# TMSS_Final.net
KiCad netlist of a schematic drawn in EAGLE
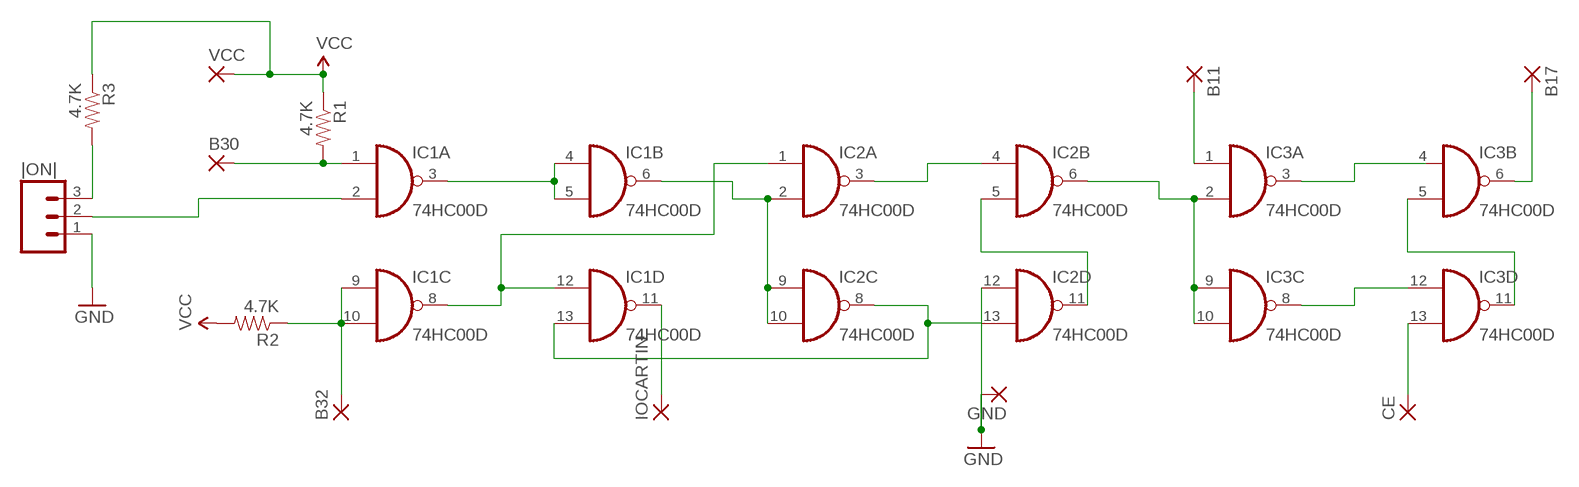
[diagram p0: schematic, sheet 1]

(export (version "E")
  (design (tool "Eeschema 10.0.6"))
  (components
    (comp (ref "B11")
      (value "1,6/0,9")
      (footprint "eagle-import:1,6_0,9")
      (libsource (lib "eagle-import") (part "1,6/0,9"))
    )
    (comp (ref "B17")
      (value "1,6/0,9")
      (footprint "eagle-import:1,6_0,9")
      (libsource (lib "eagle-import") (part "1,6/0,9"))
    )
    (comp (ref "B30")
      (value "1,6/0,9")
      (footprint "eagle-import:1,6_0,9")
      (libsource (lib "eagle-import") (part "1,6/0,9"))
    )
    (comp (ref "B32")
      (value "1,6/0,9")
      (footprint "eagle-import:1,6_0,9")
      (libsource (lib "eagle-import") (part "1,6/0,9"))
    )
    (comp (ref "CE")
      (value "1,6/0,9")
      (footprint "eagle-import:1,6_0,9")
      (libsource (lib "eagle-import") (part "1,6/0,9"))
    )
    (comp (ref "GND")
      (value "1,6/0,9")
      (footprint "eagle-import:1,6_0,9")
      (libsource (lib "eagle-import") (part "1,6/0,9"))
    )
    (comp (ref "IC1")
      (value "74HC00D")
      (footprint "eagle-import:SO14")
      (libsource (lib "eagle-import") (part "7400DHC"))
    )
    (comp (ref "IC2")
      (value "74HC00D")
      (footprint "eagle-import:SO14")
      (libsource (lib "eagle-import") (part "7400DHC"))
    )
    (comp (ref "IC3")
      (value "74HC00D")
      (footprint "eagle-import:SO14")
      (libsource (lib "eagle-import") (part "7400DHC"))
    )
    (comp (ref "IOCARTIN")
      (value "1,6/0,9")
      (footprint "eagle-import:1,6_0,9")
      (libsource (lib "eagle-import") (part "1,6/0,9"))
    )
    (comp (ref "R1")
      (value "4.7K")
      (footprint "eagle-import:0805")
      (libsource (lib "eagle-import") (part "RESISTOR0805-RES"))
    )
    (comp (ref "R2")
      (value "4.7K")
      (footprint "eagle-import:0805")
      (libsource (lib "eagle-import") (part "RESISTOR0805-RES"))
    )
    (comp (ref "R3")
      (value "4.7K")
      (footprint "eagle-import:0805")
      (libsource (lib "eagle-import") (part "RESISTOR0805-RES"))
    )
    (comp (ref "VCC")
      (value "1,6/0,9")
      (footprint "eagle-import:1,6_0,9")
      (libsource (lib "eagle-import") (part "1,6/0,9"))
    )
    (comp (ref "|ON|")
      (value "M03PTH")
      (footprint "eagle-import:1X03")
      (libsource (lib "eagle-import") (part "M03PTH"))
    )
  )
  (nets
    (net (code "1") (name "GND") (class "Default")
      (node (ref "GND") (pin "1") (pinfunction "P_1") (pintype "passive"))
      (node (ref "IC2") (pin "12") (pinfunction "I0_12") (pintype "input"))
      (node (ref "|ON|") (pin "1") (pinfunction "1_1") (pintype "passive"))
    )
    (net (code "2") (name "Net-(B11-P)") (class "Default")
      (node (ref "B11") (pin "1") (pinfunction "P_1") (pintype "passive"))
      (node (ref "IC3") (pin "1") (pinfunction "I0_1") (pintype "input"))
    )
    (net (code "3") (name "Net-(B17-P)") (class "Default")
      (node (ref "B17") (pin "1") (pinfunction "P_1") (pintype "passive"))
      (node (ref "IC3") (pin "6") (pinfunction "O_6") (pintype "output"))
    )
    (net (code "4") (name "Net-(B30-P)") (class "Default")
      (node (ref "B30") (pin "1") (pinfunction "P_1") (pintype "passive"))
      (node (ref "IC1") (pin "1") (pinfunction "I0_1") (pintype "input"))
      (node (ref "R1") (pin "2") (pinfunction "2_2") (pintype "passive"))
    )
    (net (code "5") (name "Net-(B32-P)") (class "Default")
      (node (ref "B32") (pin "1") (pinfunction "P_1") (pintype "passive"))
      (node (ref "IC1") (pin "10") (pinfunction "I1_10") (pintype "input"))
      (node (ref "IC1") (pin "9") (pinfunction "I0_9") (pintype "input"))
      (node (ref "R2") (pin "1") (pinfunction "1_1") (pintype "passive"))
    )
    (net (code "6") (name "Net-(CE-P)") (class "Default")
      (node (ref "CE") (pin "1") (pinfunction "P_1") (pintype "passive"))
      (node (ref "IC3") (pin "13") (pinfunction "I1_13") (pintype "input"))
    )
    (net (code "7") (name "Net-(IC1A-I1)") (class "Default")
      (node (ref "IC1") (pin "2") (pinfunction "I1_2") (pintype "input"))
      (node (ref "|ON|") (pin "2") (pinfunction "2_2") (pintype "passive"))
    )
    (net (code "8") (name "Net-(IC1A-O)") (class "Default")
      (node (ref "IC1") (pin "3") (pinfunction "O_3") (pintype "output"))
      (node (ref "IC1") (pin "4") (pinfunction "I0_4") (pintype "input"))
      (node (ref "IC1") (pin "5") (pinfunction "I1_5") (pintype "input"))
    )
    (net (code "9") (name "Net-(IC1B-O)") (class "Default")
      (node (ref "IC1") (pin "6") (pinfunction "O_6") (pintype "output"))
      (node (ref "IC2") (pin "10") (pinfunction "I1_10") (pintype "input"))
      (node (ref "IC2") (pin "2") (pinfunction "I1_2") (pintype "input"))
      (node (ref "IC2") (pin "9") (pinfunction "I0_9") (pintype "input"))
    )
    (net (code "10") (name "Net-(IC1C-O)") (class "Default")
      (node (ref "IC1") (pin "12") (pinfunction "I0_12") (pintype "input"))
      (node (ref "IC1") (pin "8") (pinfunction "O_8") (pintype "output"))
      (node (ref "IC2") (pin "1") (pinfunction "I0_1") (pintype "input"))
    )
    (net (code "11") (name "Net-(IC1D-I1)") (class "Default")
      (node (ref "IC1") (pin "13") (pinfunction "I1_13") (pintype "input"))
      (node (ref "IC2") (pin "13") (pinfunction "I1_13") (pintype "input"))
      (node (ref "IC2") (pin "8") (pinfunction "O_8") (pintype "output"))
    )
    (net (code "12") (name "Net-(IC1D-O)") (class "Default")
      (node (ref "IC1") (pin "11") (pinfunction "O_11") (pintype "output"))
      (node (ref "IOCARTIN") (pin "1") (pinfunction "P_1") (pintype "passive"))
    )
    (net (code "13") (name "Net-(IC2A-O)") (class "Default")
      (node (ref "IC2") (pin "3") (pinfunction "O_3") (pintype "output"))
      (node (ref "IC2") (pin "4") (pinfunction "I0_4") (pintype "input"))
    )
    (net (code "14") (name "Net-(IC2B-I1)") (class "Default")
      (node (ref "IC2") (pin "11") (pinfunction "O_11") (pintype "output"))
      (node (ref "IC2") (pin "5") (pinfunction "I1_5") (pintype "input"))
    )
    (net (code "15") (name "Net-(IC2B-O)") (class "Default")
      (node (ref "IC2") (pin "6") (pinfunction "O_6") (pintype "output"))
      (node (ref "IC3") (pin "10") (pinfunction "I1_10") (pintype "input"))
      (node (ref "IC3") (pin "2") (pinfunction "I1_2") (pintype "input"))
      (node (ref "IC3") (pin "9") (pinfunction "I0_9") (pintype "input"))
    )
    (net (code "16") (name "Net-(IC3B-I1)") (class "Default")
      (node (ref "IC3") (pin "11") (pinfunction "O_11") (pintype "output"))
      (node (ref "IC3") (pin "5") (pinfunction "I1_5") (pintype "input"))
    )
    (net (code "17") (name "Net-(IC3C-O)") (class "Default")
      (node (ref "IC3") (pin "12") (pinfunction "I0_12") (pintype "input"))
      (node (ref "IC3") (pin "8") (pinfunction "O_8") (pintype "output"))
    )
    (net (code "18") (name "Net-(R3-Pad2)") (class "Default")
      (node (ref "R3") (pin "2") (pinfunction "2_2") (pintype "passive"))
      (node (ref "|ON|") (pin "3") (pinfunction "3_3") (pintype "passive"))
    )
    (net (code "19") (name "VCC") (class "Default")
      (node (ref "R1") (pin "1") (pinfunction "1_1") (pintype "passive"))
      (node (ref "R2") (pin "2") (pinfunction "2_2") (pintype "passive"))
      (node (ref "R3") (pin "1") (pinfunction "1_1") (pintype "passive"))
      (node (ref "VCC") (pin "1") (pinfunction "P_1") (pintype "passive"))
    )
    (net (code "20") (name "unconnected-(IC3A-O-Pad3)") (class "Default")
      (node (ref "IC3") (pin "3") (pinfunction "O_3") (pintype "output"))
    )
    (net (code "21") (name "unconnected-(IC3B-I0-Pad4)") (class "Default")
      (node (ref "IC3") (pin "4") (pinfunction "I0_4") (pintype "input"))
    )
  )
)
